# BI3_Connector.net
KiCad netlist of a schematic drawn in Altium Designer
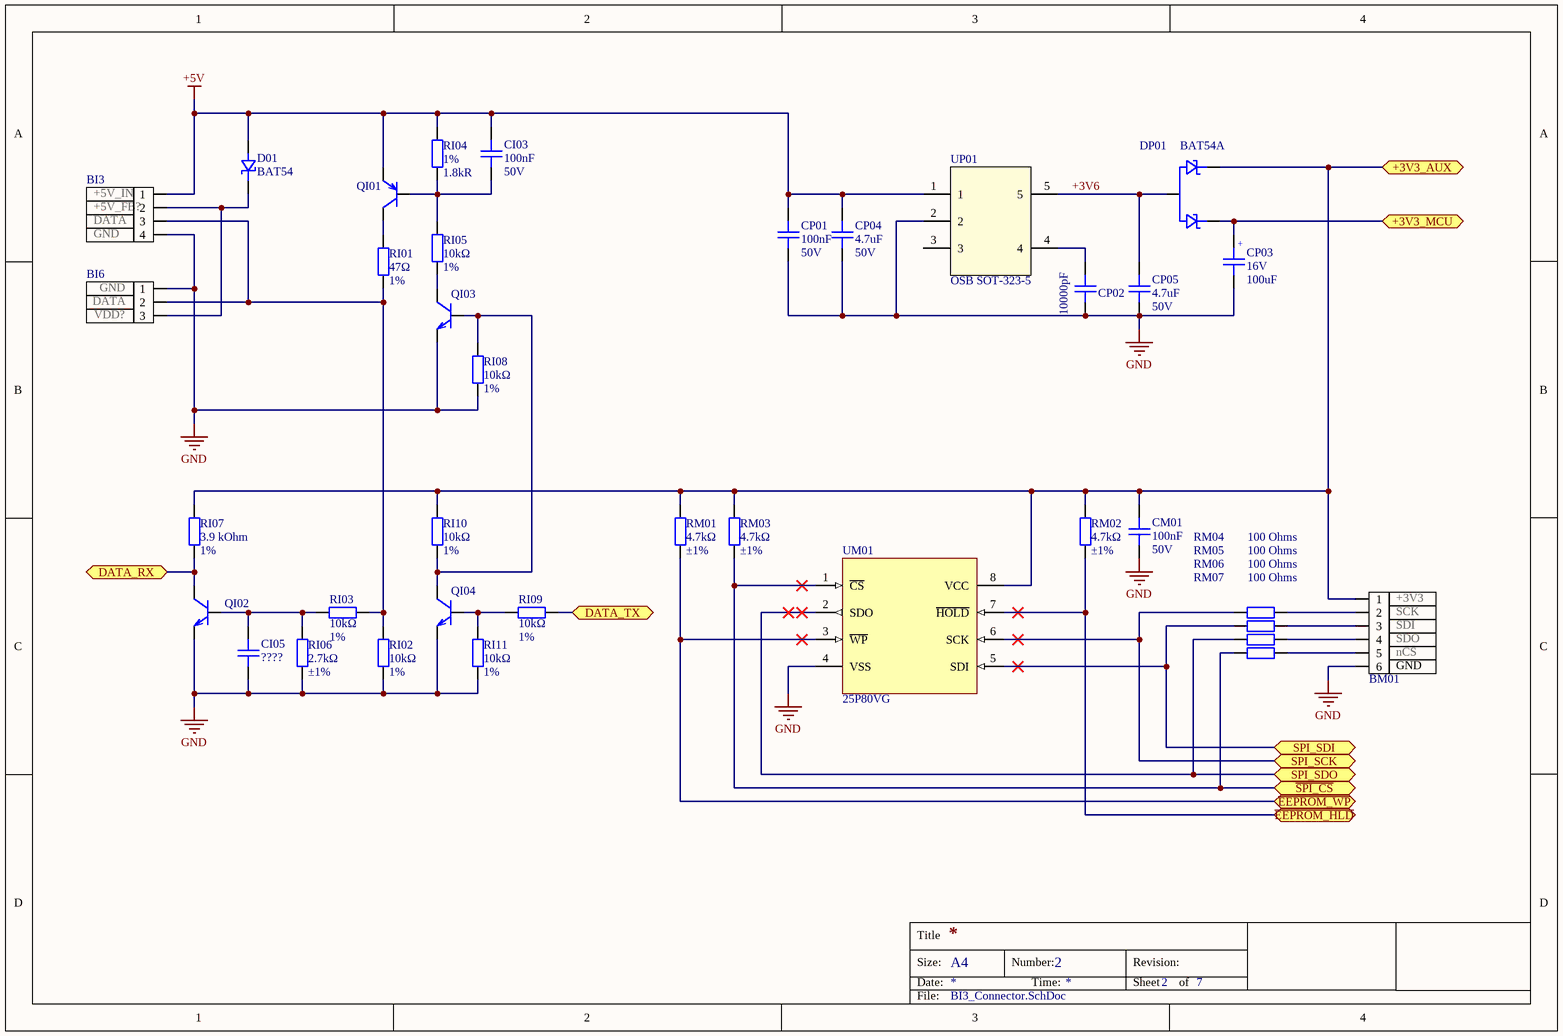
[diagram p0: BI3_Connector.SchDoc]

(export (version "E")
  (design (tool "Eeschema 10.0.6"))
  (components
    (comp (ref "BI3")
      (value "~")
      (description "Connector Header Through Hole, Right Angle 4 position 0.079\" (2.00mm)")
      (fields
        (field (name "MANUFACTURER") "Molex")
        (field (name "MANUFACTURER PART NUMBER") "53254-0470")
        (field (name "PIN_1") "+5V_IN")
        (field (name "PIN_2") "+5V_FB?")
        (field (name "PIN_3") "DATA")
        (field (name "PIN_4") "GND")
      )
      (libsource (lib "connectors_header") (part "CONN HEADER R/A 4POS 2MM"))
    )
    (comp (ref "BI6")
      (value "~")
      (footprint "CONN_S3B-ZR_JST")
      (description "Connector Header Through Hole, Right Angle 3 position 0.059\" (1.50mm)")
      (fields
        (field (name "MANUFACTURER") "JST")
        (field (name "MANUFACTURER PART NUMBER") "S3B-ZR(LF)(SN)")
        (field (name "PIN_1") "GND")
        (field (name "PIN_2") "DATA")
        (field (name "PIN_3") "VDD?")
      )
      (libsource (lib "connectors_header") (part "CONN HEADER TH R/A 3POS 1.5MM"))
    )
    (comp (ref "BM01")
      (value "~")
      (fields
        (field (name "PIN_1") "+3V3")
        (field (name "PIN_2") "SCK")
        (field (name "PIN_3") "SDI")
        (field (name "PIN_4") "SDO")
        (field (name "PIN_5") "nCS")
        (field (name "PIN_6") "GND")
      )
      (libsource (lib "connectors_header") (part "CONN HEADER EC 6POS"))
    )
    (comp (ref "CI03")
      (value "CAP CER 0.1uF ±10% 50V X7R 0603")
      (footprint "CAPC1608X08N_0603")
      (description "Capacitor")
      (fields
        (field (name "MANUFACTURER") "KEMET")
        (field (name "MANUFACTURER PART NUMBER") "C0603C104M5RACTU")
        (field (name "CAPACITANCE") "100nF")
        (field (name "VOLTAGE RATING") "50V")
      )
      (libsource (lib "capacitors_smd") (part "CAP CER 0.1uF ±10% 50V X7R 0603"))
    )
    (comp (ref "CI05")
      (value "????")
      (footprint "CAP_0603")
      (description "10000pF ±10% 100V Ceramic Capacitor X7R 0603 (1608 Metric)")
      (fields (field (name "MANUFACTURER") "Yageo") (field (name "DIGI-KEYPARTNUMBER") "311-1788-1-ND"))
      (libsource (lib "capacitors_smd") (part "CAP_CER_10000PF_100V_X7R_0603"))
    )
    (comp (ref "CM01")
      (value "CAP CER 0.1uF ±10% 50V X7R 0603")
      (footprint "CAPC1608X08N_0603")
      (description "Capacitor")
      (fields
        (field (name "MANUFACTURER") "KEMET")
        (field (name "MANUFACTURER PART NUMBER") "C0603C104M5RACTU")
        (field (name "CAPACITANCE") "100nF")
        (field (name "VOLTAGE RATING") "50V")
      )
      (libsource (lib "capacitors_smd") (part "CAP CER 0.1uF ±10% 50V X7R 0603"))
    )
    (comp (ref "CP01")
      (value "CAP CER 0.1uF ±10% 50V X7R 0603")
      (footprint "CAPC1608X08N_0603")
      (description "Capacitor")
      (fields
        (field (name "MANUFACTURER") "KEMET")
        (field (name "MANUFACTURER PART NUMBER") "C0603C104M5RACTU")
        (field (name "CAPACITANCE") "100nF")
        (field (name "VOLTAGE RATING") "50V")
      )
      (libsource (lib "capacitors_smd") (part "CAP CER 0.1uF ±10% 50V X7R 0603"))
    )
    (comp (ref "CP02")
      (value "10000pF")
      (footprint "CAP_0603")
      (description "10000pF ±10% 100V Ceramic Capacitor X7R 0603 (1608 Metric)")
      (fields (field (name "MANUFACTURER") "Yageo") (field (name "DIGI-KEYPARTNUMBER") "311-1788-1-ND"))
      (libsource (lib "capacitors_smd") (part "CAP_CER_10000PF_100V_X7R_0603"))
    )
    (comp (ref "CP03")
      (value "CAP ALUM 100 UF 20% 6.3 V SMD")
      (footprint "WCAP-ASLI_5x5.5")
      (description "100µF 6.3V Aluminum Electrolytic Capacitors Radial, Can - SMD  2000 Hrs @ 105°C")
      (fields
        (field (name "MANUFACTURER PART NUMBER") "865080142007")
        (field (name "MANUFACTURER") "Wurth Elektronik")
        (field (name "VOLTAGE RATING") "16V")
        (field (name "CAPACITANCE") "100uF")
      )
      (libsource (lib "capacitors_alum_electr_poly") (part "CAP ALUM 100 UF 20% 6.3 V SMD"))
    )
    (comp (ref "CP04")
      (value "CAP CER 4.7UF 50V X5R 0805")
      (footprint "CAPC2012X14N")
      (description "4.7µF ±10% 50V Ceramic Capacitor X5R 0805 (2012 Metric)")
      (fields
        (field (name "MANUFACTURER") "Samsung")
        (field (name "MANUFACTURER PART NUMBER") "CL21A475KBQNNNE")
        (field (name "CAPACITANCE") "4.7uF")
        (field (name "VOLTAGE RATING") "50V")
      )
      (libsource (lib "capacitors_smd") (part "CAP CER 4.7UF 50V X5R 0805"))
    )
    (comp (ref "CP05")
      (value "CAP CER 4.7UF 50V X5R 0805")
      (footprint "CAPC2012X14N")
      (description "4.7µF ±10% 50V Ceramic Capacitor X5R 0805 (2012 Metric)")
      (fields
        (field (name "MANUFACTURER") "Samsung")
        (field (name "MANUFACTURER PART NUMBER") "CL21A475KBQNNNE")
        (field (name "CAPACITANCE") "4.7uF")
        (field (name "VOLTAGE RATING") "50V")
      )
      (libsource (lib "capacitors_smd") (part "CAP CER 4.7UF 50V X5R 0805"))
    )
    (comp (ref "D01")
      (value "BAT54")
      (footprint "SOT100P240X120-3N")
      (description "Schottky DiodeS")
      (libsource (lib "diodes_schottky") (part "BAT54"))
    )
    (comp (ref "DP01")
      (value "BAT54A")
      (footprint "SOT100P240X120-3N")
      (description "410mV Forward, 70v Reverse, 1A/250mW Series Schottky Diode")
      (libsource (lib "diodes_schottky") (part "BAT54A"))
    )
    (comp (ref "QI01")
      (value "53254-0470")
      (description "Bipolar (BJT) Transistor PNP")
      (libsource (lib "bipolar-junction_transistors") (part "BC857BW"))
    )
    (comp (ref "QI02")
      (value "BC847CW,115")
      (footprint "SOT-323")
      (description "Bipolar (BJT) Transistor NPN 45V 100mA 100MHz 200mW Surface Mount SOT-323-3")
      (fields (field (name "MANUFACTURER") "Nexperia"))
      (libsource (lib "bipolar-junction_transistors") (part "TRANS BC847CW,115 NPN 45V 0.1A SOT323"))
    )
    (comp (ref "QI03")
      (value "BC847CW,115")
      (footprint "SOT-323")
      (description "Bipolar (BJT) Transistor NPN 45V 100mA 100MHz 200mW Surface Mount SOT-323-3")
      (fields (field (name "MANUFACTURER") "Nexperia"))
      (libsource (lib "bipolar-junction_transistors") (part "TRANS BC847CW,115 NPN 45V 0.1A SOT323"))
    )
    (comp (ref "QI04")
      (value "BC847CW,115")
      (footprint "SOT-323")
      (description "Bipolar (BJT) Transistor NPN 45V 100mA 100MHz 200mW Surface Mount SOT-323-3")
      (fields (field (name "MANUFACTURER") "Nexperia"))
      (libsource (lib "bipolar-junction_transistors") (part "TRANS BC847CW,115 NPN 45V 0.1A SOT323"))
    )
    (comp (ref "RI01")
      (value "R 47Ω ±1% 0603 0.1W")
      (footprint "Resistor-0603")
      (description "Resistor")
      (fields
        (field (name "MANUFACTURER") "Yageo")
        (field (name "MANUFACTURER PART NUMBER") "AC0603FR-0747RL")
        (field (name "RESISTANCE") "47Ω")
        (field (name "TOLERANCE") "1%")
      )
      (libsource (lib "resistors_smd") (part "R 47Ω ±1% 0603 0.1W"))
    )
    (comp (ref "RI02")
      (value "RES SMD 10K OHM 1% 1/10W 0603")
      (footprint "R0603")
      (description "10 kOhms ±1% 0.1W, 1/10W Chip Resistor 0603 (1608 Metric)  Thick Film")
      (fields
        (field (name "MANUFACTURER") "Yageo")
        (field (name "MANUFACTURER PART NUMBER") "RC0603FR-0710KL")
        (field (name "RESISTANCE") "10kΩ")
        (field (name "TOLERANCE") "1%")
      )
      (libsource (lib "") (part "RES SMD 10K OHM 1% 1/10W 0603_1"))
    )
    (comp (ref "RI03")
      (value "RES SMD 10K OHM 1% 1/10W 0603")
      (footprint "R0603")
      (description "10 kOhms ±1% 0.1W, 1/10W Chip Resistor 0603 (1608 Metric)  Thick Film")
      (fields
        (field (name "MANUFACTURER") "Yageo")
        (field (name "MANUFACTURER PART NUMBER") "RC0603FR-0710KL")
        (field (name "RESISTANCE") "10kΩ")
        (field (name "TOLERANCE") "1%")
      )
      (libsource (lib "resistors_smd") (part "RES SMD 10K OHM 1% 1/10W 0603"))
    )
    (comp (ref "RI04")
      (value "RES SMD 1.47K OHM 1% 1/10W 0603")
      (footprint "R0603")
      (description "1.47 kOhms ±1% 0.1W, 1/10W Chip Resistor 0603 (1608 Metric)  Thick Film")
      (fields
        (field (name "MANUFACTURER") "Yageo")
        (field (name "MANUFACTURER PART NUMBER") "RC0603FR-071K47L")
        (field (name "TOLERANCE") "1%")
        (field (name "RESISTANCE") "1.8kR")
      )
      (libsource (lib "resistors_smd") (part "RES SMD 1.47K OHM 1% 1/10W 0603"))
    )
    (comp (ref "RI05")
      (value "RES SMD 10K OHM 1% 1/10W 0603")
      (footprint "R0603")
      (description "10 kOhms ±1% 0.1W, 1/10W Chip Resistor 0603 (1608 Metric)  Thick Film")
      (fields
        (field (name "MANUFACTURER") "Yageo")
        (field (name "MANUFACTURER PART NUMBER") "RC0603FR-0710KL")
        (field (name "RESISTANCE") "10kΩ")
        (field (name "TOLERANCE") "1%")
      )
      (libsource (lib "resistors_smd") (part "RES SMD 10K OHM 1% 1/10W 0603"))
    )
    (comp (ref "RI06")
      (value "R 2.2kΩ ±1% 0603 0.1W")
      (footprint "Resistor-0603")
      (description "Resistor")
      (fields
        (field (name "MANUFACTURER") "Yageo")
        (field (name "MANUFACTURER PART NUMBER") "AC0603FR-072K2L")
        (field (name "RESISTANCE") "2.7kΩ")
        (field (name "TOLERANCE") "±1%")
      )
      (libsource (lib "resistors_smd") (part "R 2.2kΩ ±1% 0603 0.1W"))
    )
    (comp (ref "RI07")
      (value "RES SMD 7.5K OHM 1% 1/10W 0603")
      (footprint "R0603")
      (description "7.5 kOhms ±1% 0.1W, 1/10W Chip Resistor 0603 (1608 Metric) Moisture Resistant Thick Film")
      (fields
        (field (name "MANUFACTURER") "Yageo")
        (field (name "MANUFACTURER PART NUMBER") "RC0603FR-077K5L")
        (field (name "RESISTANCE") "3.9 kOhm")
        (field (name "TOLERANCE") "1%")
      )
      (libsource (lib "resistors_smd") (part "RES SMD 7.5K OHM 1% 1/10W 0603"))
    )
    (comp (ref "RI08")
      (value "RES SMD 10K OHM 1% 1/10W 0603")
      (footprint "R0603")
      (description "10 kOhms ±1% 0.1W, 1/10W Chip Resistor 0603 (1608 Metric)  Thick Film")
      (fields
        (field (name "MANUFACTURER") "Yageo")
        (field (name "MANUFACTURER PART NUMBER") "RC0603FR-0710KL")
        (field (name "RESISTANCE") "10kΩ")
        (field (name "TOLERANCE") "1%")
      )
      (libsource (lib "resistors_smd") (part "RES SMD 10K OHM 1% 1/10W 0603"))
    )
    (comp (ref "RI09")
      (value "RES SMD 10K OHM 1% 1/10W 0603")
      (footprint "R0603")
      (description "10 kOhms ±1% 0.1W, 1/10W Chip Resistor 0603 (1608 Metric)  Thick Film")
      (fields
        (field (name "MANUFACTURER") "Yageo")
        (field (name "MANUFACTURER PART NUMBER") "RC0603FR-0710KL")
        (field (name "RESISTANCE") "10kΩ")
        (field (name "TOLERANCE") "1%")
      )
      (libsource (lib "") (part "RES SMD 10K OHM 1% 1/10W 0603_3"))
    )
    (comp (ref "RI10")
      (value "RES SMD 10K OHM 1% 1/10W 0603")
      (footprint "R0603")
      (description "10 kOhms ±1% 0.1W, 1/10W Chip Resistor 0603 (1608 Metric)  Thick Film")
      (fields
        (field (name "MANUFACTURER") "Yageo")
        (field (name "MANUFACTURER PART NUMBER") "RC0603FR-0710KL")
        (field (name "RESISTANCE") "10kΩ")
        (field (name "TOLERANCE") "1%")
      )
      (libsource (lib "") (part "RES SMD 10K OHM 1% 1/10W 0603_2"))
    )
    (comp (ref "RI11")
      (value "RES SMD 10K OHM 1% 1/10W 0603")
      (footprint "R0603")
      (description "10 kOhms ±1% 0.1W, 1/10W Chip Resistor 0603 (1608 Metric)  Thick Film")
      (fields
        (field (name "MANUFACTURER") "Yageo")
        (field (name "MANUFACTURER PART NUMBER") "RC0603FR-0710KL")
        (field (name "RESISTANCE") "10kΩ")
        (field (name "TOLERANCE") "1%")
      )
      (libsource (lib "resistors_smd") (part "RES SMD 10K OHM 1% 1/10W 0603"))
    )
    (comp (ref "RM01")
      (value "~")
      (footprint "Resistor-0603")
      (description "Resistor")
      (fields
        (field (name "MANUFACTURER") "Yageo")
        (field (name "MANUFACTURER PART NUMBER") "AC0603FR-074K7L")
        (field (name "RESISTANCE") "4.7kΩ")
        (field (name "TOLERANCE") "±1%")
      )
      (libsource (lib "resistors_smd") (part "R 4.7kΩ ±1% 0603 0.1W"))
    )
    (comp (ref "RM02")
      (value "~")
      (footprint "Resistor-0603")
      (description "Resistor")
      (fields
        (field (name "MANUFACTURER") "Yageo")
        (field (name "MANUFACTURER PART NUMBER") "AC0603FR-074K7L")
        (field (name "RESISTANCE") "4.7kΩ")
        (field (name "TOLERANCE") "±1%")
      )
      (libsource (lib "resistors_smd") (part "R 4.7kΩ ±1% 0603 0.1W"))
    )
    (comp (ref "RM03")
      (value "~")
      (footprint "Resistor-0603")
      (description "Resistor")
      (fields
        (field (name "MANUFACTURER") "Yageo")
        (field (name "MANUFACTURER PART NUMBER") "AC0603FR-074K7L")
        (field (name "RESISTANCE") "4.7kΩ")
        (field (name "TOLERANCE") "±1%")
      )
      (libsource (lib "resistors_smd") (part "R 4.7kΩ ±1% 0603 0.1W"))
    )
    (comp (ref "RM04")
      (value "100 Ohms")
      (footprint "R_0603")
      (description "RES SMD 100 OHM 1% 1/8W 0603")
      (fields
        (field (name "DIGI-KEYPARTNUMBER") "MCT0603-100-CFCT-ND")
        (field (name "PARTNUMBER") "MCT06030C1000FP500")
      )
      (libsource (lib "resistors_smd") (part "RES_SMD_100_OHM_1%_1/8W_0603"))
    )
    (comp (ref "RM05")
      (value "100 Ohms")
      (footprint "R_0603")
      (description "RES SMD 100 OHM 1% 1/8W 0603")
      (fields
        (field (name "DIGI-KEYPARTNUMBER") "MCT0603-100-CFCT-ND")
        (field (name "PARTNUMBER") "MCT06030C1000FP500")
      )
      (libsource (lib "resistors_smd") (part "RES_SMD_100_OHM_1%_1/8W_0603"))
    )
    (comp (ref "RM06")
      (value "100 Ohms")
      (footprint "R_0603")
      (description "RES SMD 100 OHM 1% 1/8W 0603")
      (fields
        (field (name "DIGI-KEYPARTNUMBER") "MCT0603-100-CFCT-ND")
        (field (name "PARTNUMBER") "MCT06030C1000FP500")
      )
      (libsource (lib "resistors_smd") (part "RES_SMD_100_OHM_1%_1/8W_0603"))
    )
    (comp (ref "RM07")
      (value "100 Ohms")
      (footprint "R_0603")
      (description "RES SMD 100 OHM 1% 1/8W 0603")
      (fields
        (field (name "DIGI-KEYPARTNUMBER") "MCT0603-100-CFCT-ND")
        (field (name "PARTNUMBER") "MCT06030C1000FP500")
      )
      (libsource (lib "resistors_smd") (part "RES_SMD_100_OHM_1%_1/8W_0603"))
    )
    (comp (ref "UM01")
      (value "25P80VG")
      (libsource (lib "Anthem Projects") (part "IC 25P80VG FLASH 8MBIT SPI 75MHZ 8SO"))
    )
    (comp (ref "UP01") (value "OSB SOT-323-5") (libsource (lib "EOB68200X") (part "OSB SOT-323-5")))
  )
  (nets
    (net (code "1") (name "+5V") (class "Default")
      (node (ref "BI3") (pin "1") (pinfunction "1_1") (pintype "passive"))
      (node (ref "CI03") (pin "2") (pinfunction "2_2") (pintype "passive"))
      (node (ref "CP01") (pin "2") (pinfunction "2_2") (pintype "passive"))
      (node (ref "CP04") (pin "2") (pinfunction "2_2") (pintype "passive"))
      (node (ref "D01") (pin "1") (pinfunction "1_1") (pintype "passive"))
      (node (ref "QI01") (pin "2") (pinfunction "E_2") (pintype "passive"))
      (node (ref "RI04") (pin "2") (pinfunction "2_2") (pintype "passive"))
      (node (ref "UP01") (pin "1") (pinfunction "1_1") (pintype "passive"))
    )
    (net (code "2") (name "/+3V3_AUX") (class "Default")
      (node (ref "BM01") (pin "1") (pinfunction "1_1") (pintype "passive"))
      (node (ref "CM01") (pin "2") (pinfunction "2_2") (pintype "passive"))
      (node (ref "DP01") (pin "2") (pinfunction "2_2") (pintype "passive"))
      (node (ref "RI07") (pin "1") (pinfunction "1_1") (pintype "passive"))
      (node (ref "RI10") (pin "1") (pinfunction "1_1") (pintype "passive"))
      (node (ref "RM01") (pin "2") (pinfunction "2_2") (pintype "passive"))
      (node (ref "RM02") (pin "2") (pinfunction "2_2") (pintype "passive"))
      (node (ref "RM03") (pin "2") (pinfunction "2_2") (pintype "passive"))
      (node (ref "UM01") (pin "8") (pinfunction "VCC_8") (pintype "power_in"))
    )
    (net (code "3") (name "/+3V3_MCU") (class "Default")
      (node (ref "CP03") (pin "1") (pinfunction "1_1") (pintype "passive"))
      (node (ref "DP01") (pin "1") (pinfunction "1_1") (pintype "passive"))
    )
    (net (code "4") (name "/+3V6") (class "Default")
      (node (ref "CP05") (pin "2") (pinfunction "2_2") (pintype "passive"))
      (node (ref "DP01") (pin "3") (pinfunction "3_3") (pintype "passive"))
      (node (ref "UP01") (pin "5") (pinfunction "5_5") (pintype "passive"))
    )
    (net (code "5") (name "/DATA_RX") (class "Default")
      (node (ref "QI02") (pin "3") (pinfunction "C_3") (pintype "passive"))
      (node (ref "RI07") (pin "2") (pinfunction "2_2") (pintype "passive"))
    )
    (net (code "6") (name "/DATA_TX") (class "Default")
      (node (ref "RI09") (pin "1") (pinfunction "1_1") (pintype "passive"))
    )
    (net (code "7") (name "/EEPROM_HLD") (class "Default")
      (node (ref "RM02") (pin "1") (pinfunction "1_1") (pintype "passive"))
      (node (ref "UM01") (pin "7") (pinfunction "~{HOLD}_7") (pintype "input"))
    )
    (net (code "8") (name "/EEPROM_WP") (class "Default")
      (node (ref "RM01") (pin "1") (pinfunction "1_1") (pintype "passive"))
      (node (ref "UM01") (pin "3") (pinfunction "~{WP}_3") (pintype "input"))
    )
    (net (code "9") (name "/SPI_CS") (class "Default")
      (node (ref "RM03") (pin "1") (pinfunction "1_1") (pintype "passive"))
      (node (ref "RM07") (pin "2") (pinfunction "2_2") (pintype "passive"))
      (node (ref "UM01") (pin "1") (pinfunction "~{CS}_1") (pintype "input"))
    )
    (net (code "10") (name "/SPI_SCK") (class "Default")
      (node (ref "RM04") (pin "2") (pinfunction "2_2") (pintype "passive"))
      (node (ref "UM01") (pin "6") (pinfunction "SCK_6") (pintype "input"))
    )
    (net (code "11") (name "/SPI_SDI") (class "Default")
      (node (ref "RM05") (pin "2") (pinfunction "2_2") (pintype "passive"))
      (node (ref "UM01") (pin "5") (pinfunction "SDI_5") (pintype "input"))
    )
    (net (code "12") (name "/SPI_SDO") (class "Default")
      (node (ref "RM06") (pin "2") (pinfunction "2_2") (pintype "passive"))
      (node (ref "UM01") (pin "2") (pinfunction "SDO_2") (pintype "output"))
    )
    (net (code "13") (name "GND") (class "Default")
      (node (ref "BI3") (pin "4") (pinfunction "4_4") (pintype "passive"))
      (node (ref "BI6") (pin "1") (pinfunction "1_1") (pintype "passive"))
      (node (ref "BM01") (pin "6") (pinfunction "6_6") (pintype "passive"))
      (node (ref "CI05") (pin "1") (pinfunction "1_1") (pintype "passive"))
      (node (ref "CM01") (pin "1") (pinfunction "1_1") (pintype "passive"))
      (node (ref "CP01") (pin "1") (pinfunction "1_1") (pintype "passive"))
      (node (ref "CP02") (pin "1") (pinfunction "1_1") (pintype "passive"))
      (node (ref "CP03") (pin "2") (pinfunction "2_2") (pintype "passive"))
      (node (ref "CP04") (pin "1") (pinfunction "1_1") (pintype "passive"))
      (node (ref "CP05") (pin "1") (pinfunction "1_1") (pintype "passive"))
      (node (ref "QI02") (pin "2") (pinfunction "E_2") (pintype "passive"))
      (node (ref "QI03") (pin "2") (pinfunction "E_2") (pintype "passive"))
      (node (ref "QI04") (pin "2") (pinfunction "E_2") (pintype "passive"))
      (node (ref "RI02") (pin "1") (pinfunction "1_1") (pintype "passive"))
      (node (ref "RI06") (pin "2") (pinfunction "2_2") (pintype "passive"))
      (node (ref "RI08") (pin "1") (pinfunction "1_1") (pintype "passive"))
      (node (ref "RI11") (pin "1") (pinfunction "1_1") (pintype "passive"))
      (node (ref "UM01") (pin "4") (pinfunction "VSS_4") (pintype "power_in"))
      (node (ref "UP01") (pin "2") (pinfunction "2_2") (pintype "passive"))
    )
    (net (code "14") (name "Net-(BI3-Pad2)") (class "Default")
      (node (ref "BI3") (pin "2") (pinfunction "2_2") (pintype "passive"))
      (node (ref "BI6") (pin "3") (pinfunction "3_3") (pintype "passive"))
      (node (ref "D01") (pin "3") (pinfunction "3_3") (pintype "passive"))
    )
    (net (code "15") (name "Net-(BI3-Pad3)") (class "Default")
      (node (ref "BI3") (pin "3") (pinfunction "3_3") (pintype "passive"))
      (node (ref "BI6") (pin "2") (pinfunction "2_2") (pintype "passive"))
      (node (ref "RI01") (pin "1") (pinfunction "1_1") (pintype "passive"))
      (node (ref "RI02") (pin "2") (pinfunction "2_2") (pintype "passive"))
      (node (ref "RI03") (pin "2") (pinfunction "2_2") (pintype "passive"))
    )
    (net (code "16") (name "Net-(BM01-Pad2)") (class "Default")
      (node (ref "BM01") (pin "2") (pinfunction "2_2") (pintype "passive"))
      (node (ref "RM04") (pin "1") (pinfunction "1_1") (pintype "passive"))
    )
    (net (code "17") (name "Net-(BM01-Pad3)") (class "Default")
      (node (ref "BM01") (pin "3") (pinfunction "3_3") (pintype "passive"))
      (node (ref "RM05") (pin "1") (pinfunction "1_1") (pintype "passive"))
    )
    (net (code "18") (name "Net-(BM01-Pad4)") (class "Default")
      (node (ref "BM01") (pin "4") (pinfunction "4_4") (pintype "passive"))
      (node (ref "RM06") (pin "1") (pinfunction "1_1") (pintype "passive"))
    )
    (net (code "19") (name "Net-(BM01-Pad5)") (class "Default")
      (node (ref "BM01") (pin "5") (pinfunction "5_5") (pintype "passive"))
      (node (ref "RM07") (pin "1") (pinfunction "1_1") (pintype "passive"))
    )
    (net (code "20") (name "Net-(CP02-Pad2)") (class "Default")
      (node (ref "CP02") (pin "2") (pinfunction "2_2") (pintype "passive"))
      (node (ref "UP01") (pin "4") (pinfunction "4_4") (pintype "passive"))
    )
    (net (code "21") (name "Net-(QI01-B)") (class "Default")
      (node (ref "CI03") (pin "1") (pinfunction "1_1") (pintype "passive"))
      (node (ref "QI01") (pin "1") (pinfunction "B_1") (pintype "passive"))
      (node (ref "RI04") (pin "1") (pinfunction "1_1") (pintype "passive"))
      (node (ref "RI05") (pin "2") (pinfunction "2_2") (pintype "passive"))
    )
    (net (code "22") (name "Net-(QI01-C)") (class "Default")
      (node (ref "QI01") (pin "3") (pinfunction "C_3") (pintype "passive"))
      (node (ref "RI01") (pin "2") (pinfunction "2_2") (pintype "passive"))
    )
    (net (code "23") (name "Net-(QI02-B)") (class "Default")
      (node (ref "CI05") (pin "2") (pinfunction "2_2") (pintype "passive"))
      (node (ref "QI02") (pin "1") (pinfunction "B_1") (pintype "passive"))
      (node (ref "RI03") (pin "1") (pinfunction "1_1") (pintype "passive"))
      (node (ref "RI06") (pin "1") (pinfunction "1_1") (pintype "passive"))
    )
    (net (code "24") (name "Net-(QI03-B)") (class "Default")
      (node (ref "QI03") (pin "1") (pinfunction "B_1") (pintype "passive"))
      (node (ref "QI04") (pin "3") (pinfunction "C_3") (pintype "passive"))
      (node (ref "RI08") (pin "2") (pinfunction "2_2") (pintype "passive"))
      (node (ref "RI10") (pin "2") (pinfunction "2_2") (pintype "passive"))
    )
    (net (code "25") (name "Net-(QI03-C)") (class "Default")
      (node (ref "QI03") (pin "3") (pinfunction "C_3") (pintype "passive"))
      (node (ref "RI05") (pin "1") (pinfunction "1_1") (pintype "passive"))
    )
    (net (code "26") (name "Net-(QI04-B)") (class "Default")
      (node (ref "QI04") (pin "1") (pinfunction "B_1") (pintype "passive"))
      (node (ref "RI09") (pin "2") (pinfunction "2_2") (pintype "passive"))
      (node (ref "RI11") (pin "2") (pinfunction "2_2") (pintype "passive"))
    )
    (net (code "27") (name "unconnected-(UP01-Pad3)") (class "Default")
      (node (ref "UP01") (pin "3") (pinfunction "3_3") (pintype "passive"))
    )
  )
)
